# Lab2_Solution.net
KiCad netlist of a schematic drawn in EAGLE
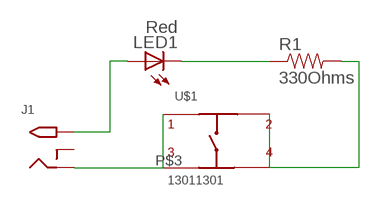
[diagram p0: schematic, sheet 1]

(export (version "E")
  (design (tool "Eeschema 10.0.6"))
  (components
    (comp (ref "J1")
      (value "2.1MMJACKTHM")
      (footprint "eagle-import:PJ-102A")
      (libsource (lib "eagle-import") (part "2.1MMJACKTHM"))
    )
    (comp (ref "LED1")
      (value "Red")
      (footprint "eagle-import:LED5MM")
      (libsource (lib "eagle-import") (part "LED5MM"))
    )
    (comp (ref "R1")
      (value "330Ohms")
      (footprint "eagle-import:AXIAL-0.3")
      (libsource (lib "eagle-import") (part "RESISTORAXIAL-0.3"))
    )
    (comp (ref "U$1")
      (value "13011301")
      (footprint "eagle-import:LSH.1301.9315")
      (libsource (lib "eagle-import") (part "13011301"))
    )
  )
  (nets
    (net (code "1") (name "Net-(J1-PadTIP)") (class "Default")
      (node (ref "J1") (pin "TIP") (pinfunction "TIP_TIP") (pintype "bidirectional"))
      (node (ref "LED1") (pin "A") (pinfunction "A_A") (pintype "passive"))
    )
    (net (code "2") (name "Net-(LED1-C)") (class "Default")
      (node (ref "LED1") (pin "K") (pinfunction "C_K") (pintype "passive"))
      (node (ref "R1") (pin "P$1") (pinfunction "1_P$1") (pintype "passive"))
    )
    (net (code "3") (name "Net-(R1-2)") (class "Default")
      (node (ref "R1") (pin "P$2") (pinfunction "2_P$2") (pintype "passive"))
      (node (ref "U$1") (pin "P$2") (pinfunction "2_P$2") (pintype "bidirectional"))
      (node (ref "U$1") (pin "P$4") (pinfunction "4_P$4") (pintype "bidirectional"))
    )
    (net (code "4") (name "Net-(U$1-1)") (class "Default")
      (node (ref "J1") (pin "RING") (pinfunction "RING_RING") (pintype "bidirectional"))
      (node (ref "U$1") (pin "P$1") (pinfunction "1_P$1") (pintype "bidirectional"))
      (node (ref "U$1") (pin "P$3") (pinfunction "3_P$3") (pintype "bidirectional"))
    )
    (net (code "5") (name "unconnected-(J1-PadRING_SW)") (class "Default")
      (node (ref "J1") (pin "RING_SW") (pinfunction "RING_SW_RING_SW") (pintype "bidirectional"))
    )
  )
)
